# PCB_TX.net
KiCad netlist of a schematic drawn in Altium Designer
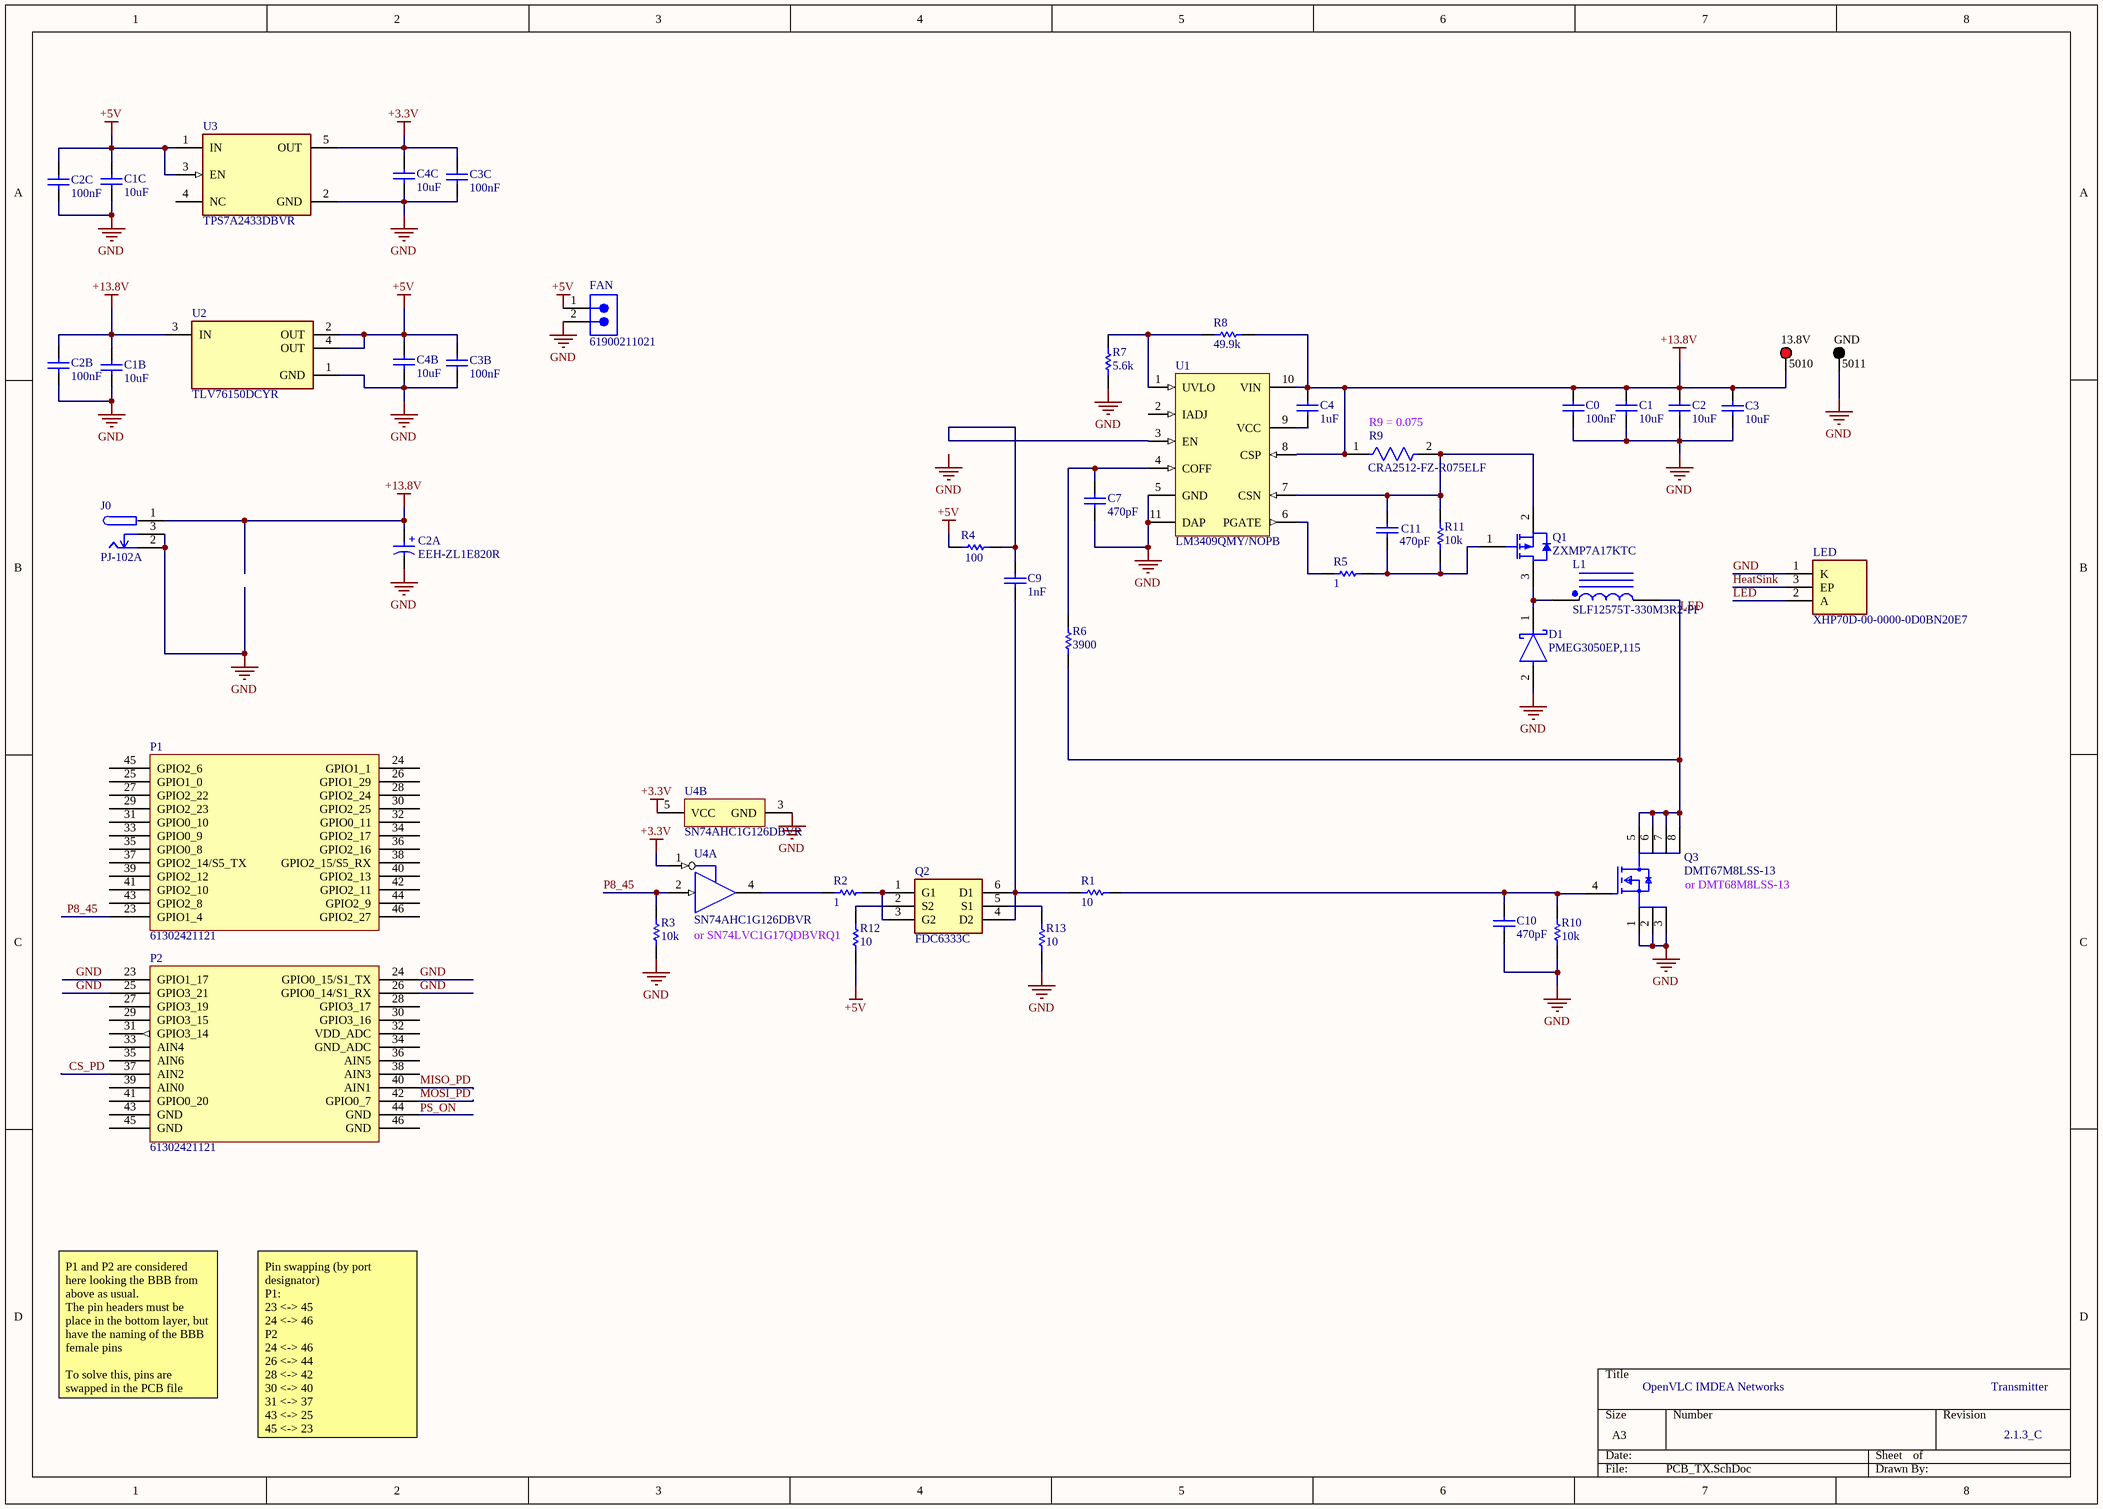
[diagram p0: PCB_TX.SchDoc]

(export (version "E")
  (design (tool "Eeschema 10.0.6"))
  (components
    (comp (ref "13.8V")
      (value "5010")
      (footprint "KSTN-5010_V")
      (description "Test Point, Red, Through Hole, RoHS, Bulk")
      (fields (field (name "MANUFACTURER") "Keystone"))
      (libsource (lib "Altium Content Vault") (part "TESTPOINT_RED"))
    )
    (comp (ref "C0")
      (value "100nF")
      (footprint "RESC1608X55N")
      (description "Capacitor")
      (fields (field (name "Comment") "GCM188R71H104KA57J") (field (name "PUBLISHER") "Altium Limited"))
      (libsource (lib "Miscellaneous Devices") (part "Cap"))
    )
    (comp (ref "C1")
      (value "10uF")
      (footprint "RESC1608X55N")
      (description "Capacitor")
      (fields (field (name "Comment") "GRM188R6YA106MA73D") (field (name "PUBLISHER") "Altium Limited"))
      (libsource (lib "Miscellaneous Devices") (part "Cap"))
    )
    (comp (ref "C1B")
      (value "10uF")
      (footprint "RESC1608X55N")
      (description "Capacitor")
      (fields (field (name "Comment") "GRM188R6YA475KE15D") (field (name "PUBLISHER") "Altium Limited"))
      (libsource (lib "Miscellaneous Devices") (part "Cap"))
    )
    (comp (ref "C1C")
      (value "10uF")
      (footprint "RESC1608X55N")
      (description "Capacitor")
      (fields (field (name "Comment") "GRM188R6YA475KE15D") (field (name "PUBLISHER") "Altium Limited"))
      (libsource (lib "Miscellaneous Devices") (part "Cap"))
    )
    (comp (ref "C2")
      (value "10uF")
      (footprint "RESC1608X55N")
      (description "Capacitor")
      (fields (field (name "Comment") "GRM188R6YA106MA73D") (field (name "PUBLISHER") "Altium Limited"))
      (libsource (lib "Miscellaneous Devices") (part "Cap"))
    )
    (comp (ref "C2A")
      (value "EEH-ZL1E820R")
      (footprint "WCAP-PSLP_D5H5.5")
      (description "875105242006 WCAP-PSLP Aluminum Polymer Capacitors")
      (fields (field (name "TOLERANCE") "20%"))
      (libsource (lib "Altium Content Vault") (part "Capacitor_Polarized"))
    )
    (comp (ref "C2B")
      (value "100nF")
      (footprint "RESC1608X55N")
      (description "Capacitor")
      (fields (field (name "Comment") "GRM188R6YA106MA73D") (field (name "PUBLISHER") "Altium Limited"))
      (libsource (lib "Miscellaneous Devices") (part "Cap"))
    )
    (comp (ref "C2C")
      (value "100nF")
      (footprint "RESC1608X55N")
      (description "Capacitor")
      (fields (field (name "Comment") "GRM188R6YA106MA73D") (field (name "PUBLISHER") "Altium Limited"))
      (libsource (lib "Miscellaneous Devices") (part "Cap"))
    )
    (comp (ref "C3")
      (value "10uF")
      (footprint "RESC1608X55N")
      (description "Capacitor")
      (fields (field (name "Comment") "GRM188R6YA106MA73D") (field (name "PUBLISHER") "Altium Limited"))
      (libsource (lib "Miscellaneous Devices") (part "Cap"))
    )
    (comp (ref "C3B")
      (value "100nF")
      (footprint "RESC1608X55N")
      (description "Capacitor")
      (fields (field (name "Comment") "GCM188R71H104KA57J") (field (name "PUBLISHER") "Altium Limited"))
      (libsource (lib "Miscellaneous Devices") (part "Cap"))
    )
    (comp (ref "C3C")
      (value "100nF")
      (footprint "RESC1608X55N")
      (description "Capacitor")
      (fields (field (name "Comment") "GCM188R71H104KA57J") (field (name "PUBLISHER") "Altium Limited"))
      (libsource (lib "Miscellaneous Devices") (part "Cap"))
    )
    (comp (ref "C4")
      (value "1uF")
      (footprint "RESC1608X55N")
      (description "Capacitor")
      (fields (field (name "Comment") "GCM188D71H105KE36J") (field (name "PUBLISHER") "Altium Limited"))
      (libsource (lib "Miscellaneous Devices") (part "Cap"))
    )
    (comp (ref "C4B")
      (value "10uF")
      (footprint "RESC1608X55N")
      (description "Capacitor")
      (fields (field (name "Comment") "GRM188R6YA106MA73D") (field (name "PUBLISHER") "Altium Limited"))
      (libsource (lib "Miscellaneous Devices") (part "Cap"))
    )
    (comp (ref "C4C")
      (value "10uF")
      (footprint "RESC1608X55N")
      (description "Capacitor")
      (fields (field (name "Comment") "GRM188R6YA106MA73D") (field (name "PUBLISHER") "Altium Limited"))
      (libsource (lib "Miscellaneous Devices") (part "Cap"))
    )
    (comp (ref "C7")
      (value "470pF")
      (footprint "RESC1608X55N")
      (description "Capacitor")
      (fields (field (name "Comment") "GCM1885C1H471JA16D") (field (name "PUBLISHER") "Altium Limited"))
      (libsource (lib "Miscellaneous Devices") (part "Cap"))
    )
    (comp (ref "C9")
      (value "1nF")
      (footprint "RESC1608X55N")
      (description "Capacitor")
      (fields (field (name "Comment") "GRM1885C1H102JA01D") (field (name "PUBLISHER") "Altium Limited"))
      (libsource (lib "Miscellaneous Devices") (part "Cap"))
    )
    (comp (ref "C10")
      (value "470pF")
      (footprint "RESC1608X55N")
      (description "Capacitor")
      (fields (field (name "Comment") "GCM1885C1H471JA16D") (field (name "PUBLISHER") "Altium Limited"))
      (libsource (lib "Miscellaneous Devices") (part "Cap"))
    )
    (comp (ref "C11")
      (value "470pF")
      (footprint "RESC1608X55N")
      (description "Capacitor")
      (fields (field (name "Comment") "GCM1885C1H471JA16D") (field (name "PUBLISHER") "Altium Limited"))
      (libsource (lib "Miscellaneous Devices") (part "Cap"))
    )
    (comp (ref "D1")
      (value "PMEG3050EP,115")
      (footprint "FP-SOD128-MFG")
      (description "DIODE SCHOTTKY 30V 5A SOD128")
      (libsource (lib "Altium Content Vault") (part "1d6ec82d83fb6aee721767c19dac4b9"))
    )
    (comp (ref "FAN")
      (value "61900211021")
      (footprint "61900211021")
      (libsource (lib "Altium Content Vault") (part "Header_Male_1R_02P"))
    )
    (comp (ref "GND")
      (value "5011")
      (footprint "KSTN-5011_V")
      (description "Test Point, Black, Through Hole, RoHS, Bulk")
      (fields (field (name "MANUFACTURER") "Keystone"))
      (libsource (lib "Altium Content Vault") (part "TESTPOINT_BLACK"))
    )
    (comp (ref "J0")
      (value "PJ-102A")
      (footprint "FP-PJ-102A-MFG")
      (description "PJ-102A 2.0 x 6.5 mm, 2.5 A, Horizontal, Through Hole, Tapered Pins, Dc Power Jack Connector")
      (libsource (lib "Altium Content Vault") (part "c639f672d24b5d70918fa8d934b95d1"))
    )
    (comp (ref "L1")
      (value "SLF12575T-330M3R2-PF")
      (footprint "EATN-DR125_V")
      (fields (field (name "MANUFACTURER") "EATON"))
      (libsource (lib "Altium Content Vault") (part "IND-DOT-2"))
    )
    (comp (ref "LED")
      (value "XHP70D-00-0000-0D0BN20E7")
      (footprint "XHP70DH000000D0HN20E3_12")
      (description "High Power LEDs - White White 5000 K 80-CRI, XLamp XHP70D")
      (fields
        (field (name "MANUFACTURER_PART_NUMBER") "XHP70D-H0-0000-0D0HN20E3")
        (field (name "MOUSER PART NUMBER") "941-XHP70DH0D0HN20E3")
      )
      (libsource (lib "XHP70D-H0-0000-0D0HN20E3") (part "XHP70D-H0-0000-0D0HN20E3"))
    )
    (comp (ref "P1")
      (value "61302421121")
      (footprint "BBB_CAPE_NO_HEADER_R_24")
      (libsource (lib "BeagleBoneCape") (part "BBB_P8_reduced"))
    )
    (comp (ref "P2")
      (value "61302421121")
      (footprint "BBB_CAPE_NO_HEADER_R_24")
      (libsource (lib "BeagleBoneCape") (part "BBB_P9_reduced"))
    )
    (comp (ref "Q1")
      (value "ZXMP7A17KTC")
      (footprint "DIOD-TO252-3_V")
      (fields (field (name "MANUFACTURER") "Diodes Inc"))
      (libsource (lib "Altium Content Vault") (part "PEMOS-GSD-3"))
    )
    (comp (ref "Q2")
      (value "FDC6333C")
      (footprint "SOT95P275X110-6N")
      (fields (field (name "MOUSER PART NUMBER") "512-FDC6333C"))
      (libsource (lib "FDC6333C") (part "FDC6333C"))
    )
    (comp (ref "Q3")
      (value "DMT67M8LSS-13")
      (footprint "FP-751EB-MFG")
      (description "FDS2672-F085 Trans MOSFET N-CH 200V 3.9A Automotive 8-Pin SOIC T/R")
      (libsource (lib "Altium Content Vault") (part "a2191056e8335feadc5ee6660ea8eee"))
    )
    (comp (ref "R1")
      (value "10")
      (footprint "RESC1608X55N")
      (description "Resistor")
      (fields (field (name "Comment") "RT0603BRD0710RL") (field (name "PUBLISHER") "Altium Limited"))
      (libsource (lib "Miscellaneous Devices") (part "Res1"))
    )
    (comp (ref "R2")
      (value "1")
      (footprint "RESC1608X55N")
      (description "Resistor")
      (fields (field (name "Comment") "RT0603BRD071RL") (field (name "PUBLISHER") "Altium Limited"))
      (libsource (lib "Miscellaneous Devices") (part "Res1"))
    )
    (comp (ref "R3")
      (value "10k")
      (footprint "RESC1608X55N")
      (description "Resistor")
      (fields (field (name "Comment") "RT0603BRD0710KL") (field (name "PUBLISHER") "Altium Limited"))
      (libsource (lib "Miscellaneous Devices") (part "Res1"))
    )
    (comp (ref "R4")
      (value "100")
      (footprint "RESC1608X55N")
      (description "Resistor")
      (fields (field (name "Comment") "RT0603BRD07100RL") (field (name "PUBLISHER") "Altium Limited"))
      (libsource (lib "Miscellaneous Devices") (part "Res1"))
    )
    (comp (ref "R5")
      (value "1")
      (footprint "RESC1608X55N")
      (description "Resistor")
      (fields (field (name "Comment") "RT0603BRD0710RL") (field (name "PUBLISHER") "Altium Limited"))
      (libsource (lib "Miscellaneous Devices") (part "Res1"))
    )
    (comp (ref "R6")
      (value "3900")
      (footprint "RESC1608X55N")
      (description "Resistor")
      (fields (field (name "Comment") "RT0603BRD073K9L") (field (name "PUBLISHER") "Altium Limited"))
      (libsource (lib "Miscellaneous Devices") (part "Res1"))
    )
    (comp (ref "R7")
      (value "5.6k")
      (footprint "RESC1608X55N")
      (description "Resistor")
      (fields (field (name "Comment") "RT0603BRD075K76L") (field (name "PUBLISHER") "Altium Limited"))
      (libsource (lib "Miscellaneous Devices") (part "Res1"))
    )
    (comp (ref "R8")
      (value "49.9k")
      (footprint "RESC1608X55N")
      (description "Resistor")
      (fields (field (name "Comment") "RT0603BRD0749K9L") (field (name "PUBLISHER") "Altium Limited"))
      (libsource (lib "Miscellaneous Devices") (part "Res1"))
    )
    (comp (ref "R9")
      (value "CRA2512-FZ-R075ELF")
      (footprint "FP-CSRN2512-IPC_B")
      (description "Res Thick Film 2512 0.1Ω 1% 2W ±200ppm/°C Molded SMD Plastic T/R")
      (fields (field (name "TOLERANCE") "1%"))
      (libsource (lib "Altium Content Vault") (part "1029c3af85768c4190bb7ad29bc67b5"))
    )
    (comp (ref "R10")
      (value "10k")
      (footprint "RESC1608X55N")
      (description "Resistor")
      (fields (field (name "Comment") "RT0603BRD0710KL") (field (name "PUBLISHER") "Altium Limited"))
      (libsource (lib "Miscellaneous Devices") (part "Res1"))
    )
    (comp (ref "R11")
      (value "10k")
      (footprint "RESC1608X55N")
      (description "Resistor")
      (fields (field (name "Comment") "RT0603BRD0710KL") (field (name "PUBLISHER") "Altium Limited"))
      (libsource (lib "Miscellaneous Devices") (part "Res1"))
    )
    (comp (ref "R12")
      (value "10")
      (footprint "RESC1608X55N")
      (description "Resistor")
      (fields (field (name "Comment") "RT0603BRD0710RL") (field (name "PUBLISHER") "Altium Limited"))
      (libsource (lib "Miscellaneous Devices") (part "Res1"))
    )
    (comp (ref "R13")
      (value "10")
      (footprint "RESC1608X55N")
      (description "Resistor")
      (fields (field (name "Comment") "RT0603BRD0710RL") (field (name "PUBLISHER") "Altium Limited"))
      (libsource (lib "Miscellaneous Devices") (part "Res1"))
    )
    (comp (ref "U1")
      (value "LM3409QMY/NOPB")
      (footprint "DGQ0010A_N")
      (description "PFET Buck Controller for High Power LED Drives, 10-pin eMSOP, Pb-Free")
      (fields (field (name "MANUFACTURER") "Texas Instruments"))
      (libsource (lib "Altium Content Vault") (part "IN-LEDD-LM3409-11"))
    )
    (comp (ref "U2")
      (value "TLV76150DCYR")
      (footprint "FP-DCY0004A-MFG")
      (description "TLV76150DCYR 1-A 16-V high-PSRR linear voltage regulator 4-SOT-223 -40 to 125")
      (libsource (lib "Altium Content Vault") (part "991ffb903c51cf6179ce9942c0606aa"))
    )
    (comp (ref "U3")
      (value "TPS7A2433DBVR")
      (footprint "FP-DBV0005A-MFG")
      (libsource (lib "Altium Content Vault") (part "ee7747973c1ed1d4cccbb20406fa51c"))
    )
    (comp (ref "U4")
      (value "SN74AHC1G126DBVR")
      (footprint "DBV0005A_M")
      (description "Single Bus Buffer Gate With 3-State Outputs, DBV0005A, LARGE T&R")
      (fields
        (field (name "GENERIC PART NUMBER") "SN74AHC1G126")
        (field (name "MANUFACTURER") "Texas Instruments")
      )
      (libsource (lib "Altium Content Vault") (part "TI-SN74XXXXXX126-5"))
    )
  )
  (nets
    (net (code "1") (name "+3.3V") (class "Default")
      (node (ref "C3C") (pin "1") (pinfunction "1_1") (pintype "passive"))
      (node (ref "C4C") (pin "2") (pinfunction "2_2") (pintype "passive"))
      (node (ref "U3") (pin "5") (pinfunction "OUT_5") (pintype "power_in"))
      (node (ref "U4") (pin "1") (pinfunction "OE_1") (pintype "input"))
      (node (ref "U4") (pin "5") (pinfunction "VCC_5") (pintype "power_in"))
    )
    (net (code "2") (name "+5V") (class "Default")
      (node (ref "C1C") (pin "2") (pinfunction "2_2") (pintype "passive"))
      (node (ref "C2C") (pin "1") (pinfunction "1_1") (pintype "passive"))
      (node (ref "C3B") (pin "1") (pinfunction "1_1") (pintype "passive"))
      (node (ref "C4B") (pin "2") (pinfunction "2_2") (pintype "passive"))
      (node (ref "FAN") (pin "1") (pinfunction "1_1") (pintype "passive"))
      (node (ref "R12") (pin "2") (pinfunction "2_2") (pintype "passive"))
      (node (ref "R4") (pin "2") (pinfunction "2_2") (pintype "passive"))
      (node (ref "U2") (pin "2") (pinfunction "OUT_2") (pintype "passive"))
      (node (ref "U2") (pin "4") (pinfunction "OUT_4") (pintype "passive"))
      (node (ref "U3") (pin "1") (pinfunction "IN_1") (pintype "power_in"))
      (node (ref "U3") (pin "3") (pinfunction "EN_3") (pintype "input"))
    )
    (net (code "3") (name "+13.8V") (class "Default")
      (node (ref "13.8V") (pin "1") (pinfunction "1_1") (pintype "passive"))
      (node (ref "C0") (pin "1") (pinfunction "1_1") (pintype "passive"))
      (node (ref "C1") (pin "1") (pinfunction "1_1") (pintype "passive"))
      (node (ref "C1B") (pin "2") (pinfunction "2_2") (pintype "passive"))
      (node (ref "C2") (pin "1") (pinfunction "1_1") (pintype "passive"))
      (node (ref "C2A") (pin "1") (pinfunction "P_1") (pintype "passive"))
      (node (ref "C2B") (pin "1") (pinfunction "1_1") (pintype "passive"))
      (node (ref "C3") (pin "1") (pinfunction "1_1") (pintype "passive"))
      (node (ref "C4") (pin "1") (pinfunction "1_1") (pintype "passive"))
      (node (ref "J0") (pin "1") (pinfunction "1_1") (pintype "passive"))
      (node (ref "R8") (pin "1") (pinfunction "1_1") (pintype "passive"))
      (node (ref "R9") (pin "1") (pinfunction "1_1") (pintype "passive"))
      (node (ref "U1") (pin "10") (pinfunction "VIN_10") (pintype "power_in"))
      (node (ref "U1") (pin "8") (pinfunction "CSP_8") (pintype "input"))
      (node (ref "U2") (pin "3") (pinfunction "IN_3") (pintype "power_in"))
    )
    (net (code "4") (name "/CS_PD") (class "Default")
      (node (ref "P2") (pin "37") (pinfunction "AIN2_37") (pintype "passive"))
    )
    (net (code "5") (name "/HeatSink") (class "Default")
      (node (ref "LED") (pin "3") (pinfunction "EP_3") (pintype "passive"))
    )
    (net (code "6") (name "/LED") (class "Default")
      (node (ref "L1") (pin "2") (pinfunction "2_2") (pintype "passive"))
      (node (ref "LED") (pin "2") (pinfunction "A_2") (pintype "passive"))
      (node (ref "Q3") (pin "5") (pinfunction "D_5") (pintype "passive"))
      (node (ref "Q3") (pin "6") (pinfunction "D_6") (pintype "passive"))
      (node (ref "Q3") (pin "7") (pinfunction "D_7") (pintype "passive"))
      (node (ref "Q3") (pin "8") (pinfunction "D_8") (pintype "passive"))
      (node (ref "R6") (pin "2") (pinfunction "2_2") (pintype "passive"))
    )
    (net (code "7") (name "/MISO_PD") (class "Default")
      (node (ref "P2") (pin "40") (pinfunction "AIN1_40") (pintype "passive"))
    )
    (net (code "8") (name "/MOSI_PD") (class "Default")
      (node (ref "P2") (pin "42") (pinfunction "GPIO0_7_42") (pintype "passive"))
    )
    (net (code "9") (name "/P8_45") (class "Default")
      (node (ref "P1") (pin "23") (pinfunction "GPIO1_4_23") (pintype "passive"))
      (node (ref "R3") (pin "1") (pinfunction "1_1") (pintype "passive"))
      (node (ref "U4") (pin "2") (pinfunction "A_2") (pintype "input"))
    )
    (net (code "11") (name "GND") (class "Default")
      (node (ref "C0") (pin "2") (pinfunction "2_2") (pintype "passive"))
      (node (ref "C1") (pin "2") (pinfunction "2_2") (pintype "passive"))
      (node (ref "C10") (pin "2") (pinfunction "2_2") (pintype "passive"))
      (node (ref "C1B") (pin "1") (pinfunction "1_1") (pintype "passive"))
      (node (ref "C1C") (pin "1") (pinfunction "1_1") (pintype "passive"))
      (node (ref "C2") (pin "2") (pinfunction "2_2") (pintype "passive"))
      (node (ref "C2A") (pin "2") (pinfunction "N_2") (pintype "passive"))
      (node (ref "C2B") (pin "2") (pinfunction "2_2") (pintype "passive"))
      (node (ref "C2C") (pin "2") (pinfunction "2_2") (pintype "passive"))
      (node (ref "C3") (pin "2") (pinfunction "2_2") (pintype "passive"))
      (node (ref "C3B") (pin "2") (pinfunction "2_2") (pintype "passive"))
      (node (ref "C3C") (pin "2") (pinfunction "2_2") (pintype "passive"))
      (node (ref "C4B") (pin "1") (pinfunction "1_1") (pintype "passive"))
      (node (ref "C4C") (pin "1") (pinfunction "1_1") (pintype "passive"))
      (node (ref "C7") (pin "2") (pinfunction "2_2") (pintype "passive"))
      (node (ref "D1") (pin "2") (pinfunction "A_2") (pintype "passive"))
      (node (ref "FAN") (pin "2") (pinfunction "2_2") (pintype "passive"))
      (node (ref "GND") (pin "1") (pinfunction "1_1") (pintype "passive"))
      (node (ref "J0") (pin "2") (pinfunction "2_2") (pintype "passive"))
      (node (ref "J0") (pin "3") (pinfunction "3_3") (pintype "passive"))
      (node (ref "LED") (pin "1") (pinfunction "K_1") (pintype "passive"))
      (node (ref "P2") (pin "23") (pinfunction "GPIO1_17_23") (pintype "passive"))
      (node (ref "P2") (pin "24") (pinfunction "GPIO0_15/S1_TX_24") (pintype "passive"))
      (node (ref "P2") (pin "25") (pinfunction "GPIO3_21_25") (pintype "passive"))
      (node (ref "P2") (pin "26") (pinfunction "GPIO0_14/S1_RX_26") (pintype "passive"))
      (node (ref "Q3") (pin "1") (pinfunction "S_1") (pintype "passive"))
      (node (ref "Q3") (pin "2") (pinfunction "S_2") (pintype "passive"))
      (node (ref "Q3") (pin "3") (pinfunction "S_3") (pintype "passive"))
      (node (ref "R10") (pin "2") (pinfunction "2_2") (pintype "passive"))
      (node (ref "R13") (pin "2") (pinfunction "2_2") (pintype "passive"))
      (node (ref "R3") (pin "2") (pinfunction "2_2") (pintype "passive"))
      (node (ref "R7") (pin "2") (pinfunction "2_2") (pintype "passive"))
      (node (ref "U1") (pin "11") (pinfunction "DAP_11") (pintype "power_in"))
      (node (ref "U1") (pin "5") (pinfunction "GND_5") (pintype "power_in"))
      (node (ref "U2") (pin "1") (pinfunction "GND_1") (pintype "power_in"))
      (node (ref "U3") (pin "2") (pinfunction "GND_2") (pintype "power_in"))
      (node (ref "U4") (pin "3") (pinfunction "GND_3") (pintype "power_in"))
    )
    (net (code "12") (name "Net-(D1-C)") (class "Default")
      (node (ref "D1") (pin "1") (pinfunction "C_1") (pintype "passive"))
      (node (ref "L1") (pin "1") (pinfunction "1_1") (pintype "passive"))
      (node (ref "Q1") (pin "3") (pinfunction "DRAIN_3") (pintype "passive"))
    )
    (net (code "13") (name "Net-(Q1-GATE)") (class "Default")
      (node (ref "C11") (pin "2") (pinfunction "2_2") (pintype "passive"))
      (node (ref "Q1") (pin "1") (pinfunction "GATE_1") (pintype "passive"))
      (node (ref "R11") (pin "2") (pinfunction "2_2") (pintype "passive"))
      (node (ref "R5") (pin "1") (pinfunction "1_1") (pintype "passive"))
    )
    (net (code "14") (name "Net-(Q1-SOURCE)") (class "Default")
      (node (ref "C11") (pin "1") (pinfunction "1_1") (pintype "passive"))
      (node (ref "Q1") (pin "2") (pinfunction "SOURCE_2") (pintype "passive"))
      (node (ref "R11") (pin "1") (pinfunction "1_1") (pintype "passive"))
      (node (ref "R9") (pin "2") (pinfunction "2_2") (pintype "passive"))
      (node (ref "U1") (pin "7") (pinfunction "CSN_7") (pintype "input"))
    )
    (net (code "15") (name "Net-(Q2-D1)") (class "Default")
      (node (ref "C9") (pin "2") (pinfunction "2_2") (pintype "passive"))
      (node (ref "Q2") (pin "4") (pinfunction "D2_4") (pintype "passive"))
      (node (ref "Q2") (pin "6") (pinfunction "D1_6") (pintype "passive"))
      (node (ref "R1") (pin "2") (pinfunction "2_2") (pintype "passive"))
    )
    (net (code "16") (name "Net-(Q2-G1)") (class "Default")
      (node (ref "Q2") (pin "1") (pinfunction "G1_1") (pintype "passive"))
      (node (ref "Q2") (pin "3") (pinfunction "G2_3") (pintype "passive"))
      (node (ref "R2") (pin "1") (pinfunction "1_1") (pintype "passive"))
    )
    (net (code "17") (name "Net-(Q2-S1)") (class "Default")
      (node (ref "Q2") (pin "5") (pinfunction "S1_5") (pintype "passive"))
      (node (ref "R13") (pin "1") (pinfunction "1_1") (pintype "passive"))
    )
    (net (code "18") (name "Net-(Q2-S2)") (class "Default")
      (node (ref "Q2") (pin "2") (pinfunction "S2_2") (pintype "passive"))
      (node (ref "R12") (pin "1") (pinfunction "1_1") (pintype "passive"))
    )
    (net (code "19") (name "Net-(Q3-G)") (class "Default")
      (node (ref "C10") (pin "1") (pinfunction "1_1") (pintype "passive"))
      (node (ref "Q3") (pin "4") (pinfunction "G_4") (pintype "passive"))
      (node (ref "R1") (pin "1") (pinfunction "1_1") (pintype "passive"))
      (node (ref "R10") (pin "1") (pinfunction "1_1") (pintype "passive"))
    )
    (net (code "20") (name "Net-(U1-COFF)") (class "Default")
      (node (ref "C7") (pin "1") (pinfunction "1_1") (pintype "passive"))
      (node (ref "R6") (pin "1") (pinfunction "1_1") (pintype "passive"))
      (node (ref "U1") (pin "4") (pinfunction "COFF_4") (pintype "input"))
    )
    (net (code "21") (name "Net-(U1-EN)") (class "Default")
      (node (ref "C9") (pin "1") (pinfunction "1_1") (pintype "passive"))
      (node (ref "R4") (pin "1") (pinfunction "1_1") (pintype "passive"))
      (node (ref "U1") (pin "3") (pinfunction "EN_3") (pintype "input"))
    )
    (net (code "22") (name "Net-(U1-PGATE)") (class "Default")
      (node (ref "R5") (pin "2") (pinfunction "2_2") (pintype "passive"))
      (node (ref "U1") (pin "6") (pinfunction "PGATE_6") (pintype "output"))
    )
    (net (code "23") (name "Net-(U1-UVLO)") (class "Default")
      (node (ref "R7") (pin "1") (pinfunction "1_1") (pintype "passive"))
      (node (ref "R8") (pin "2") (pinfunction "2_2") (pintype "passive"))
      (node (ref "U1") (pin "1") (pinfunction "UVLO_1") (pintype "input"))
    )
    (net (code "24") (name "Net-(U1-VCC)") (class "Default")
      (node (ref "C4") (pin "2") (pinfunction "2_2") (pintype "passive"))
      (node (ref "U1") (pin "9") (pinfunction "VCC_9") (pintype "power_in"))
    )
    (net (code "25") (name "Net-(U4A-Y)") (class "Default")
      (node (ref "R2") (pin "2") (pinfunction "2_2") (pintype "passive"))
      (node (ref "U4") (pin "4") (pinfunction "Y_4") (pintype "tri_state"))
    )
    (net (code "26") (name "unconnected-(P1-GPIO0_8-Pad35)") (class "Default")
      (node (ref "P1") (pin "35") (pinfunction "GPIO0_8_35") (pintype "passive"))
    )
    (net (code "27") (name "unconnected-(P1-GPIO0_9-Pad33)") (class "Default")
      (node (ref "P1") (pin "33") (pinfunction "GPIO0_9_33") (pintype "passive"))
    )
    (net (code "28") (name "unconnected-(P1-GPIO0_10-Pad31)") (class "Default")
      (node (ref "P1") (pin "31") (pinfunction "GPIO0_10_31") (pintype "passive"))
    )
    (net (code "29") (name "unconnected-(P1-GPIO0_11-Pad32)") (class "Default")
      (node (ref "P1") (pin "32") (pinfunction "GPIO0_11_32") (pintype "passive"))
    )
    (net (code "30") (name "unconnected-(P1-GPIO1_0-Pad25)") (class "Default")
      (node (ref "P1") (pin "25") (pinfunction "GPIO1_0_25") (pintype "passive"))
    )
    (net (code "31") (name "unconnected-(P1-GPIO1_1-Pad24)") (class "Default")
      (node (ref "P1") (pin "24") (pinfunction "GPIO1_1_24") (pintype "passive"))
    )
    (net (code "32") (name "unconnected-(P1-GPIO1_29-Pad26)") (class "Default")
      (node (ref "P1") (pin "26") (pinfunction "GPIO1_29_26") (pintype "passive"))
    )
    (net (code "33") (name "unconnected-(P1-GPIO2_6-Pad45)") (class "Default")
      (node (ref "P1") (pin "45") (pinfunction "GPIO2_6_45") (pintype "passive"))
    )
    (net (code "34") (name "unconnected-(P1-GPIO2_8-Pad43)") (class "Default")
      (node (ref "P1") (pin "43") (pinfunction "GPIO2_8_43") (pintype "passive"))
    )
    (net (code "35") (name "unconnected-(P1-GPIO2_9-Pad44)") (class "Default")
      (node (ref "P1") (pin "44") (pinfunction "GPIO2_9_44") (pintype "passive"))
    )
    (net (code "36") (name "unconnected-(P1-GPIO2_10-Pad41)") (class "Default")
      (node (ref "P1") (pin "41") (pinfunction "GPIO2_10_41") (pintype "passive"))
    )
    (net (code "37") (name "unconnected-(P1-GPIO2_11-Pad42)") (class "Default")
      (node (ref "P1") (pin "42") (pinfunction "GPIO2_11_42") (pintype "passive"))
    )
    (net (code "38") (name "unconnected-(P1-GPIO2_12-Pad39)") (class "Default")
      (node (ref "P1") (pin "39") (pinfunction "GPIO2_12_39") (pintype "passive"))
    )
    (net (code "39") (name "unconnected-(P1-GPIO2_13-Pad40)") (class "Default")
      (node (ref "P1") (pin "40") (pinfunction "GPIO2_13_40") (pintype "passive"))
    )
    (net (code "40") (name "unconnected-(P1-GPIO2_14{slash}S5_TX-Pad37)") (class "Default")
      (node (ref "P1") (pin "37") (pinfunction "GPIO2_14/S5_TX_37") (pintype "passive"))
    )
    (net (code "41") (name "unconnected-(P1-GPIO2_15{slash}S5_RX-Pad38)") (class "Default")
      (node (ref "P1") (pin "38") (pinfunction "GPIO2_15/S5_RX_38") (pintype "passive"))
    )
    (net (code "42") (name "unconnected-(P1-GPIO2_16-Pad36)") (class "Default")
      (node (ref "P1") (pin "36") (pinfunction "GPIO2_16_36") (pintype "passive"))
    )
    (net (code "43") (name "unconnected-(P1-GPIO2_17-Pad34)") (class "Default")
      (node (ref "P1") (pin "34") (pinfunction "GPIO2_17_34") (pintype "passive"))
    )
    (net (code "44") (name "unconnected-(P1-GPIO2_22-Pad27)") (class "Default")
      (node (ref "P1") (pin "27") (pinfunction "GPIO2_22_27") (pintype "passive"))
    )
    (net (code "45") (name "unconnected-(P1-GPIO2_23-Pad29)") (class "Default")
      (node (ref "P1") (pin "29") (pinfunction "GPIO2_23_29") (pintype "passive"))
    )
    (net (code "46") (name "unconnected-(P1-GPIO2_24-Pad28)") (class "Default")
      (node (ref "P1") (pin "28") (pinfunction "GPIO2_24_28") (pintype "passive"))
    )
    (net (code "47") (name "unconnected-(P1-GPIO2_25-Pad30)") (class "Default")
      (node (ref "P1") (pin "30") (pinfunction "GPIO2_25_30") (pintype "passive"))
    )
    (net (code "48") (name "unconnected-(P1-GPIO2_27-Pad46)") (class "Default")
      (node (ref "P1") (pin "46") (pinfunction "GPIO2_27_46") (pintype "passive"))
    )
    (net (code "49") (name "unconnected-(P2-AIN0-Pad39)") (class "Default")
      (node (ref "P2") (pin "39") (pinfunction "AIN0_39") (pintype "passive"))
    )
    (net (code "50") (name "unconnected-(P2-AIN3-Pad38)") (class "Default")
      (node (ref "P2") (pin "38") (pinfunction "AIN3_38") (pintype "passive"))
    )
    (net (code "51") (name "unconnected-(P2-AIN4-Pad33)") (class "Default")
      (node (ref "P2") (pin "33") (pinfunction "AIN4_33") (pintype "passive"))
    )
    (net (code "52") (name "unconnected-(P2-AIN5-Pad36)") (class "Default")
      (node (ref "P2") (pin "36") (pinfunction "AIN5_36") (pintype "passive"))
    )
    (net (code "53") (name "unconnected-(P2-AIN6-Pad35)") (class "Default")
      (node (ref "P2") (pin "35") (pinfunction "AIN6_35") (pintype "passive"))
    )
    (net (code "54") (name "unconnected-(P2-GND-Pad43)") (class "Default")
      (node (ref "P2") (pin "43") (pinfunction "GND_43") (pintype "passive"))
    )
    (net (code "55") (name "unconnected-(P2-GND-Pad44)") (class "Default")
      (node (ref "P2") (pin "44") (pinfunction "GND_44") (pintype "passive"))
    )
    (net (code "56") (name "unconnected-(P2-GND-Pad45)") (class "Default")
      (node (ref "P2") (pin "45") (pinfunction "GND_45") (pintype "passive"))
    )
    (net (code "57") (name "unconnected-(P2-GND-Pad46)") (class "Default")
      (node (ref "P2") (pin "46") (pinfunction "GND_46") (pintype "passive"))
    )
    (net (code "58") (name "unconnected-(P2-GND_ADC-Pad34)") (class "Default")
      (node (ref "P2") (pin "34") (pinfunction "GND_ADC_34") (pintype "passive"))
    )
    (net (code "59") (name "unconnected-(P2-GPIO0_20-Pad41)") (class "Default")
      (node (ref "P2") (pin "41") (pinfunction "GPIO0_20_41") (pintype "passive"))
    )
    (net (code "60") (name "unconnected-(P2-GPIO3_14-Pad31)") (class "Default")
      (node (ref "P2") (pin "31") (pinfunction "GPIO3_14_31") (pintype "output"))
    )
    (net (code "61") (name "unconnected-(P2-GPIO3_15-Pad29)") (class "Default")
      (node (ref "P2") (pin "29") (pinfunction "GPIO3_15_29") (pintype "passive"))
    )
    (net (code "62") (name "unconnected-(P2-GPIO3_16-Pad30)") (class "Default")
      (node (ref "P2") (pin "30") (pinfunction "GPIO3_16_30") (pintype "passive"))
    )
    (net (code "63") (name "unconnected-(P2-GPIO3_17-Pad28)") (class "Default")
      (node (ref "P2") (pin "28") (pinfunction "GPIO3_17_28") (pintype "passive"))
    )
    (net (code "64") (name "unconnected-(P2-GPIO3_19-Pad27)") (class "Default")
      (node (ref "P2") (pin "27") (pinfunction "GPIO3_19_27") (pintype "passive"))
    )
    (net (code "65") (name "unconnected-(P2-VDD_ADC-Pad32)") (class "Default")
      (node (ref "P2") (pin "32") (pinfunction "VDD_ADC_32") (pintype "passive"))
    )
    (net (code "66") (name "unconnected-(U1-IADJ-Pad2)") (class "Default")
      (node (ref "U1") (pin "2") (pinfunction "IADJ_2") (pintype "input"))
    )
    (net (code "67") (name "unconnected-(U3-NC-Pad4)") (class "Default")
      (node (ref "U3") (pin "4") (pinfunction "NC_4") (pintype "passive"))
    )
  )
)
